# ADC.net
KiCad netlist of a schematic drawn in Altium Designer
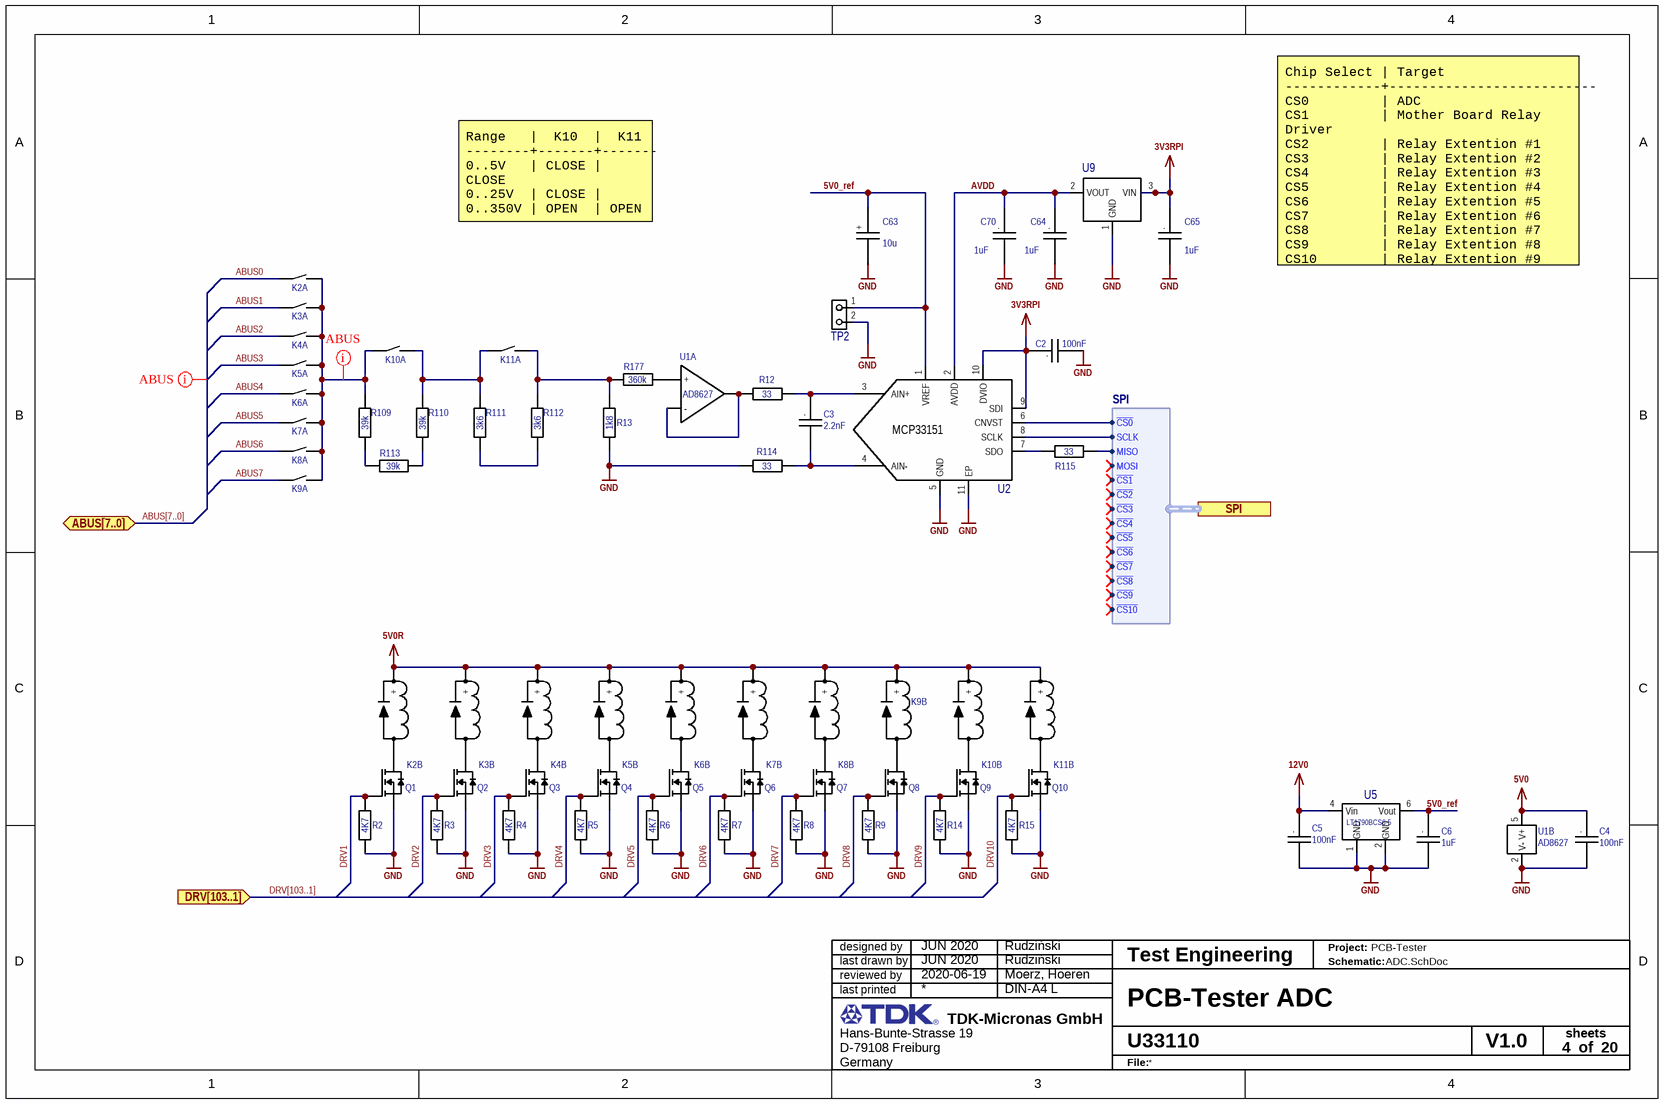
[diagram p0: ADC.SchDoc]

(export (version "E")
  (design (tool "Eeschema 10.0.6"))
  (components
    (comp (ref "C2")
      (value "100nF")
      (footprint "C0402 Reflow")
      (description "CAP CER 0.1UF 25V X7R 0402")
      (fields
        (field (name "TOLERANCE") "±5%")
        (field (name "02. DISTRIBUTOR PART NUMBER") "311-2077-6-ND")
        (field (name "13. CREATED DATE/NAME") "AUG2018/Hören")
      )
      (libsource (lib "chickenfood") (part "C"))
    )
    (comp (ref "C3")
      (value "2.2nF")
      (footprint "C0603 Reflow")
      (description "CAP CER 2200PF 50V X7R 0402")
      (fields
        (field (name "TOLERANCE") "±5%")
        (field (name "02. DISTRIBUTOR PART NUMBER") "1276-1532-6-ND")
        (field (name "13. CREATED DATE/NAME") "AUG2018/Hören")
      )
      (libsource (lib "chickenfood") (part "C"))
    )
    (comp (ref "C4")
      (value "100nF")
      (footprint "C0402 Reflow")
      (description "CAP CER 0.1UF 25V X7R 0402")
      (fields
        (field (name "TOLERANCE") "±5%")
        (field (name "02. DISTRIBUTOR PART NUMBER") "311-2077-6-ND")
        (field (name "13. CREATED DATE/NAME") "AUG2018/Hören")
      )
      (libsource (lib "chickenfood") (part "C"))
    )
    (comp (ref "C5")
      (value "100nF")
      (footprint "C0402 Reflow")
      (description "CAP CER 0.1UF 25V X7R 0402")
      (fields
        (field (name "TOLERANCE") "±5%")
        (field (name "02. DISTRIBUTOR PART NUMBER") "311-2077-6-ND")
        (field (name "13. CREATED DATE/NAME") "AUG2018/Hören")
      )
      (libsource (lib "chickenfood") (part "C"))
    )
    (comp (ref "C6")
      (value "1uF")
      (footprint "C0402 Reflow")
      (description "CAP CER 1UF 6.3V X7R 0402")
      (fields
        (field (name "TOLERANCE") "±10%")
        (field (name "02. DISTRIBUTOR PART NUMBER") "490-13339-6-ND")
        (field (name "13. CREATED DATE/NAME") "AUG2018/Hören")
      )
      (libsource (lib "chickenfood") (part "C"))
    )
    (comp (ref "C63")
      (value "10u")
      (footprint "CAP_TAN_B")
      (description "CAP TANT 10UF 20% 16V 1411")
      (fields
        (field (name "02. DISTRIBUTOR PART NUMBER") "718-2344-1-ND")
        (field (name "07. MANUFACTURER  PART NUMBER") "TMCHB1C106MTRF")
      )
      (libsource (lib "PCB-Tester-Board-V1") (part "C+_TAN"))
    )
    (comp (ref "C64")
      (value "1uF")
      (footprint "C0402 Reflow")
      (description "CAP CER 1UF 6.3V X7R 0402")
      (fields
        (field (name "TOLERANCE") "±10%")
        (field (name "02. DISTRIBUTOR PART NUMBER") "490-13339-6-ND")
        (field (name "13. CREATED DATE/NAME") "AUG2018/Hören")
      )
      (libsource (lib "chickenfood") (part "C"))
    )
    (comp (ref "C65")
      (value "1uF")
      (footprint "C0402 Reflow")
      (description "CAP CER 1UF 6.3V X7R 0402")
      (fields
        (field (name "TOLERANCE") "±10%")
        (field (name "02. DISTRIBUTOR PART NUMBER") "490-13339-6-ND")
        (field (name "13. CREATED DATE/NAME") "AUG2018/Hören")
      )
      (libsource (lib "chickenfood") (part "C"))
    )
    (comp (ref "C70")
      (value "1uF")
      (footprint "C0402 Reflow")
      (description "CAP CER 1UF 6.3V X7R 0402")
      (fields
        (field (name "TOLERANCE") "±10%")
        (field (name "02. DISTRIBUTOR PART NUMBER") "490-13339-6-ND")
        (field (name "13. CREATED DATE/NAME") "AUG2018/Hören")
      )
      (libsource (lib "chickenfood") (part "C"))
    )
    (comp (ref "K2")
      (value "K")
      (footprint "118-1A")
      (description "5V Signal Relais, Normal Open")
      (fields
        (field (name "02. DISTRIBUTOR PART NUMBER") "118-1-A-5/2D")
        (field (name "13. CREATED DATE/NAME") "20.12.17 S. Kaiser")
      )
      (libsource (lib "chickenfood") (part "118-1-A-5/2D"))
    )
    (comp (ref "K3")
      (value "K")
      (footprint "118-1A")
      (description "5V Signal Relais, Normal Open")
      (fields
        (field (name "02. DISTRIBUTOR PART NUMBER") "118-1-A-5/2D")
        (field (name "13. CREATED DATE/NAME") "20.12.17 S. Kaiser")
      )
      (libsource (lib "chickenfood") (part "118-1-A-5/2D"))
    )
    (comp (ref "K4")
      (value "K")
      (footprint "118-1A")
      (description "5V Signal Relais, Normal Open")
      (fields
        (field (name "02. DISTRIBUTOR PART NUMBER") "118-1-A-5/2D")
        (field (name "13. CREATED DATE/NAME") "20.12.17 S. Kaiser")
      )
      (libsource (lib "") (part "118-1-A-5/2D_1"))
    )
    (comp (ref "K5")
      (value "K")
      (footprint "118-1A")
      (description "5V Signal Relais, Normal Open")
      (fields
        (field (name "02. DISTRIBUTOR PART NUMBER") "118-1-A-5/2D")
        (field (name "13. CREATED DATE/NAME") "20.12.17 S. Kaiser")
      )
      (libsource (lib "chickenfood") (part "118-1-A-5/2D"))
    )
    (comp (ref "K6")
      (value "K")
      (footprint "118-1A")
      (description "5V Signal Relais, Normal Open")
      (fields
        (field (name "02. DISTRIBUTOR PART NUMBER") "118-1-A-5/2D")
        (field (name "13. CREATED DATE/NAME") "20.12.17 S. Kaiser")
      )
      (libsource (lib "") (part "118-1-A-5/2D_1"))
    )
    (comp (ref "K7")
      (value "K")
      (footprint "118-1A")
      (description "5V Signal Relais, Normal Open")
      (fields
        (field (name "02. DISTRIBUTOR PART NUMBER") "118-1-A-5/2D")
        (field (name "13. CREATED DATE/NAME") "20.12.17 S. Kaiser")
      )
      (libsource (lib "chickenfood") (part "118-1-A-5/2D"))
    )
    (comp (ref "K8")
      (value "K")
      (footprint "118-1A")
      (description "5V Signal Relais, Normal Open")
      (fields
        (field (name "02. DISTRIBUTOR PART NUMBER") "118-1-A-5/2D")
        (field (name "13. CREATED DATE/NAME") "20.12.17 S. Kaiser")
      )
      (libsource (lib "chickenfood") (part "118-1-A-5/2D"))
    )
    (comp (ref "K9")
      (value "K")
      (footprint "118-1A")
      (description "5V Signal Relais, Normal Open")
      (fields
        (field (name "02. DISTRIBUTOR PART NUMBER") "118-1-A-5/2D")
        (field (name "13. CREATED DATE/NAME") "20.12.17 S. Kaiser")
      )
      (libsource (lib "") (part "118-1-A-5/2D_1"))
    )
    (comp (ref "K10")
      (value "K")
      (footprint "118-1A")
      (description "5V Signal Relais, Normal Open")
      (fields
        (field (name "02. DISTRIBUTOR PART NUMBER") "118-1-A-5/2D")
        (field (name "13. CREATED DATE/NAME") "20.12.17 S. Kaiser")
      )
      (libsource (lib "chickenfood") (part "118-1-A-5/2D"))
    )
    (comp (ref "K11")
      (value "K")
      (footprint "118-1A")
      (description "5V Signal Relais, Normal Open")
      (fields
        (field (name "02. DISTRIBUTOR PART NUMBER") "118-1-A-5/2D")
        (field (name "13. CREATED DATE/NAME") "20.12.17 S. Kaiser")
      )
      (libsource (lib "chickenfood") (part "118-1-A-5/2D"))
    )
    (comp (ref "Q1")
      (value "Q")
      (footprint "SOT23-3")
      (description "MOSFET N-CH 25V 680MA SOT-23")
      (fields
        (field (name "02. DISTRIBUTOR PART NUMBER") "FDV303NDKR-ND")
        (field (name "07. MANUFACTURER  PART NUMBER") "FDV303N")
        (field (name "13. CREATED DATE/NAME") "AUG 2018 / Hören")
      )
      (libsource (lib "SCT8-Board1") (part "FDV303N"))
    )
    (comp (ref "Q2")
      (value "Q")
      (footprint "SOT23-3")
      (description "MOSFET N-CH 25V 680MA SOT-23")
      (fields
        (field (name "02. DISTRIBUTOR PART NUMBER") "FDV303NDKR-ND")
        (field (name "07. MANUFACTURER  PART NUMBER") "FDV303N")
        (field (name "13. CREATED DATE/NAME") "AUG 2018 / Hören")
      )
      (libsource (lib "SCT8-Board1") (part "FDV303N"))
    )
    (comp (ref "Q3")
      (value "Q")
      (footprint "SOT23-3")
      (description "MOSFET N-CH 25V 680MA SOT-23")
      (fields
        (field (name "02. DISTRIBUTOR PART NUMBER") "FDV303NDKR-ND")
        (field (name "07. MANUFACTURER  PART NUMBER") "FDV303N")
        (field (name "13. CREATED DATE/NAME") "AUG 2018 / Hören")
      )
      (libsource (lib "SCT8-Board1") (part "FDV303N"))
    )
    (comp (ref "Q4")
      (value "Q")
      (footprint "SOT23-3")
      (description "MOSFET N-CH 25V 680MA SOT-23")
      (fields
        (field (name "02. DISTRIBUTOR PART NUMBER") "FDV303NDKR-ND")
        (field (name "07. MANUFACTURER  PART NUMBER") "FDV303N")
        (field (name "13. CREATED DATE/NAME") "AUG 2018 / Hören")
      )
      (libsource (lib "SCT8-Board1") (part "FDV303N"))
    )
    (comp (ref "Q5")
      (value "Q")
      (footprint "SOT23-3")
      (description "MOSFET N-CH 25V 680MA SOT-23")
      (fields
        (field (name "02. DISTRIBUTOR PART NUMBER") "FDV303NDKR-ND")
        (field (name "07. MANUFACTURER  PART NUMBER") "FDV303N")
        (field (name "13. CREATED DATE/NAME") "AUG 2018 / Hören")
      )
      (libsource (lib "SCT8-Board1") (part "FDV303N"))
    )
    (comp (ref "Q6")
      (value "Q")
      (footprint "SOT23-3")
      (description "MOSFET N-CH 25V 680MA SOT-23")
      (fields
        (field (name "02. DISTRIBUTOR PART NUMBER") "FDV303NDKR-ND")
        (field (name "07. MANUFACTURER  PART NUMBER") "FDV303N")
        (field (name "13. CREATED DATE/NAME") "AUG 2018 / Hören")
      )
      (libsource (lib "SCT8-Board1") (part "FDV303N"))
    )
    (comp (ref "Q7")
      (value "Q")
      (footprint "SOT23-3")
      (description "MOSFET N-CH 25V 680MA SOT-23")
      (fields
        (field (name "02. DISTRIBUTOR PART NUMBER") "FDV303NDKR-ND")
        (field (name "07. MANUFACTURER  PART NUMBER") "FDV303N")
        (field (name "13. CREATED DATE/NAME") "AUG 2018 / Hören")
      )
      (libsource (lib "SCT8-Board1") (part "FDV303N"))
    )
    (comp (ref "Q8")
      (value "Q")
      (footprint "SOT23-3")
      (description "MOSFET N-CH 25V 680MA SOT-23")
      (fields
        (field (name "02. DISTRIBUTOR PART NUMBER") "FDV303NDKR-ND")
        (field (name "07. MANUFACTURER  PART NUMBER") "FDV303N")
        (field (name "13. CREATED DATE/NAME") "AUG 2018 / Hören")
      )
      (libsource (lib "SCT8-Board1") (part "FDV303N"))
    )
    (comp (ref "Q9")
      (value "Q")
      (footprint "SOT23-3")
      (description "MOSFET N-CH 25V 680MA SOT-23")
      (fields
        (field (name "02. DISTRIBUTOR PART NUMBER") "FDV303NDKR-ND")
        (field (name "07. MANUFACTURER  PART NUMBER") "FDV303N")
        (field (name "13. CREATED DATE/NAME") "AUG 2018 / Hören")
      )
      (libsource (lib "SCT8-Board1") (part "FDV303N"))
    )
    (comp (ref "Q10")
      (value "Q")
      (footprint "SOT23-3")
      (description "MOSFET N-CH 25V 680MA SOT-23")
      (fields
        (field (name "02. DISTRIBUTOR PART NUMBER") "FDV303NDKR-ND")
        (field (name "07. MANUFACTURER  PART NUMBER") "FDV303N")
        (field (name "13. CREATED DATE/NAME") "AUG 2018 / Hören")
      )
      (libsource (lib "SCT8-Board1") (part "FDV303N"))
    )
    (comp (ref "R2")
      (value "4K7")
      (footprint "R0603 Reflow")
      (description "RES SMD 4.7K OHM 1% 1/10W 0603")
      (fields
        (field (name "TOLERANCE") "±1%")
        (field (name "02. DISTRIBUTOR PART NUMBER") "311-4.70KHRCT-ND")
        (field (name "13. CREATED DATE/NAME") "AUG2018/Hören")
      )
      (libsource (lib "chickenfood") (part "R"))
    )
    (comp (ref "R3")
      (value "4K7")
      (footprint "R0603 Reflow")
      (description "RES SMD 4.7K OHM 1% 1/10W 0603")
      (fields
        (field (name "TOLERANCE") "±1%")
        (field (name "02. DISTRIBUTOR PART NUMBER") "311-4.70KHRCT-ND")
        (field (name "13. CREATED DATE/NAME") "AUG2018/Hören")
      )
      (libsource (lib "chickenfood") (part "R"))
    )
    (comp (ref "R4")
      (value "4K7")
      (footprint "R0603 Reflow")
      (description "RES SMD 4.7K OHM 1% 1/10W 0603")
      (fields
        (field (name "TOLERANCE") "±1%")
        (field (name "02. DISTRIBUTOR PART NUMBER") "311-4.70KHRCT-ND")
        (field (name "13. CREATED DATE/NAME") "AUG2018/Hören")
      )
      (libsource (lib "chickenfood") (part "R"))
    )
    (comp (ref "R5")
      (value "4K7")
      (footprint "R0603 Reflow")
      (description "RES SMD 4.7K OHM 1% 1/10W 0603")
      (fields
        (field (name "TOLERANCE") "±1%")
        (field (name "02. DISTRIBUTOR PART NUMBER") "311-4.70KHRCT-ND")
        (field (name "13. CREATED DATE/NAME") "AUG2018/Hören")
      )
      (libsource (lib "chickenfood") (part "R"))
    )
    (comp (ref "R6")
      (value "4K7")
      (footprint "R0603 Reflow")
      (description "RES SMD 4.7K OHM 1% 1/10W 0603")
      (fields
        (field (name "TOLERANCE") "±1%")
        (field (name "02. DISTRIBUTOR PART NUMBER") "311-4.70KHRCT-ND")
        (field (name "13. CREATED DATE/NAME") "AUG2018/Hören")
      )
      (libsource (lib "chickenfood") (part "R"))
    )
    (comp (ref "R7")
      (value "4K7")
      (footprint "R0603 Reflow")
      (description "RES SMD 4.7K OHM 1% 1/10W 0603")
      (fields
        (field (name "TOLERANCE") "±1%")
        (field (name "02. DISTRIBUTOR PART NUMBER") "311-4.70KHRCT-ND")
        (field (name "13. CREATED DATE/NAME") "AUG2018/Hören")
      )
      (libsource (lib "chickenfood") (part "R"))
    )
    (comp (ref "R8")
      (value "4K7")
      (footprint "R0603 Reflow")
      (description "RES SMD 4.7K OHM 1% 1/10W 0603")
      (fields
        (field (name "TOLERANCE") "±1%")
        (field (name "02. DISTRIBUTOR PART NUMBER") "311-4.70KHRCT-ND")
        (field (name "13. CREATED DATE/NAME") "AUG2018/Hören")
      )
      (libsource (lib "chickenfood") (part "R"))
    )
    (comp (ref "R9")
      (value "4K7")
      (footprint "R0603 Reflow")
      (description "RES SMD 4.7K OHM 1% 1/10W 0603")
      (fields
        (field (name "TOLERANCE") "±1%")
        (field (name "02. DISTRIBUTOR PART NUMBER") "311-4.70KHRCT-ND")
        (field (name "13. CREATED DATE/NAME") "AUG2018/Hören")
      )
      (libsource (lib "chickenfood") (part "R"))
    )
    (comp (ref "R12")
      (value "33")
      (footprint "R0402 Reflow")
      (description "RES SMD 33 OHM 1% 1/16W 0402")
      (fields
        (field (name "TOLERANCE") "±1%")
        (field (name "02. DISTRIBUTOR PART NUMBER") "311-33.0LRDKR-ND")
        (field (name "13. CREATED DATE/NAME") "AUG2018/Hören")
      )
      (libsource (lib "") (part "R_1"))
    )
    (comp (ref "R13")
      (value "1k8")
      (footprint "R0603 Reflow")
      (description "RES SMD 1.8K OHM 1% 1/16W 0402")
      (fields
        (field (name "TOLERANCE") "±1%")
        (field (name "02. DISTRIBUTOR PART NUMBER") "311-1.80KLRCT-ND")
        (field (name "13. CREATED DATE/NAME") "AUG2018/Hören")
      )
      (libsource (lib "chickenfood") (part "R"))
    )
    (comp (ref "R14")
      (value "4K7")
      (footprint "R0603 Reflow")
      (description "RES SMD 4.7K OHM 1% 1/10W 0603")
      (fields
        (field (name "TOLERANCE") "±1%")
        (field (name "02. DISTRIBUTOR PART NUMBER") "311-4.70KHRCT-ND")
        (field (name "13. CREATED DATE/NAME") "AUG2018/Hören")
      )
      (libsource (lib "chickenfood") (part "R"))
    )
    (comp (ref "R15")
      (value "4K7")
      (footprint "R0603 Reflow")
      (description "RES SMD 4.7K OHM 1% 1/10W 0603")
      (fields
        (field (name "TOLERANCE") "±1%")
        (field (name "02. DISTRIBUTOR PART NUMBER") "311-4.70KHRCT-ND")
        (field (name "13. CREATED DATE/NAME") "AUG2018/Hören")
      )
      (libsource (lib "chickenfood") (part "R"))
    )
    (comp (ref "R109")
      (value "39k")
      (footprint "R2512 Reflow")
      (description "CRGP 2512 39K 1%")
      (fields
        (field (name "TOLERANCE") "±1%")
        (field (name "02. DISTRIBUTOR PART NUMBER") "A130740CT-ND")
        (field (name "13. CREATED DATE/NAME") "AUG2018/Hören")
      )
      (libsource (lib "PCB-Tester-Board-V1") (part "R"))
    )
    (comp (ref "R110")
      (value "39k")
      (footprint "R2512 Reflow")
      (description "CRGP 2512 39K 1%")
      (fields
        (field (name "TOLERANCE") "±1%")
        (field (name "02. DISTRIBUTOR PART NUMBER") "A130740CT-ND")
        (field (name "13. CREATED DATE/NAME") "AUG2018/Hören")
      )
      (libsource (lib "PCB-Tester-Board-V1") (part "R"))
    )
    (comp (ref "R111")
      (value "3k6")
      (footprint "R0603 Reflow")
      (description "RES SMD 3.6K OHM 1% 1/10W 0603")
      (fields
        (field (name "TOLERANCE") "±1%")
        (field (name "02. DISTRIBUTOR PART NUMBER") "311-3.60KHRCT-ND")
        (field (name "13. CREATED DATE/NAME") "AUG2018/Hören")
      )
      (libsource (lib "PCB-Tester-Board-V1") (part "R"))
    )
    (comp (ref "R112")
      (value "3k6")
      (footprint "R0603 Reflow")
      (description "RES SMD 3.6K OHM 1% 1/10W 0603")
      (fields
        (field (name "TOLERANCE") "±1%")
        (field (name "02. DISTRIBUTOR PART NUMBER") "311-3.60KHRCT-ND")
        (field (name "13. CREATED DATE/NAME") "AUG2018/Hören")
      )
      (libsource (lib "PCB-Tester-Board-V1") (part "R"))
    )
    (comp (ref "R113")
      (value "39k")
      (footprint "R2512 Reflow")
      (description "CRGP 2512 39K 1%")
      (fields
        (field (name "TOLERANCE") "±1%")
        (field (name "02. DISTRIBUTOR PART NUMBER") "A130740CT-ND")
        (field (name "13. CREATED DATE/NAME") "AUG2018/Hören")
      )
      (libsource (lib "") (part "R_1"))
    )
    (comp (ref "R114")
      (value "33")
      (footprint "R0402 Reflow")
      (description "RES SMD 33 OHM 1% 1/16W 0402")
      (fields
        (field (name "TOLERANCE") "±1%")
        (field (name "02. DISTRIBUTOR PART NUMBER") "311-33.0LRDKR-ND")
        (field (name "13. CREATED DATE/NAME") "AUG2018/Hören")
      )
      (libsource (lib "") (part "R_1"))
    )
    (comp (ref "R115")
      (value "33")
      (footprint "R0402 Reflow")
      (description "RES SMD 33 OHM 1% 1/16W 0402")
      (fields
        (field (name "TOLERANCE") "±1%")
        (field (name "02. DISTRIBUTOR PART NUMBER") "311-33.0LRDKR-ND")
        (field (name "13. CREATED DATE/NAME") "AUG2018/Hören")
      )
      (libsource (lib "PCB-Tester-Board-V1") (part "R_19"))
    )
    (comp (ref "R177")
      (value "360k")
      (footprint "R1206 Reflow")
      (description "RES SMD 360K OHM 1% 1/4W 1206")
      (fields
        (field (name "TOLERANCE") "±1%")
        (field (name "02. DISTRIBUTOR PART NUMBER") "311-360KFRCT-ND")
        (field (name "13. CREATED DATE/NAME") "AUG2018/Hören")
      )
      (libsource (lib "") (part "R_1"))
    )
    (comp (ref "TP2")
      (value "TP")
      (footprint "DualTestpoint 100mils")
      (description "Dual testpoint, pitch 2.54mm")
      (fields
        (field (name "02. DISTRIBUTOR PART NUMBER") "HMTSW-103-07-G-S-240")
        (field (name "13. CREATED DATE/NAME") "AUG2018/Hören")
      )
      (libsource (lib "PCB-Tester-Board-V1") (part "DualTestpoint 100mils"))
    )
    (comp (ref "U1")
      (value "U")
      (footprint "tom:SC70-5")
      (description "IC OPAMP JFET 5MHZ RRO SC70-5")
      (fields
        (field (name "02. DISTRIBUTOR PART NUMBER") "AD8627AKSZ-R2DKR-ND")
        (field (name "07. MANUFACTURER  PART NUMBER") "AD8627AKSZ-R2")
        (field (name "PART") "AD8627")
        (field (name "13. CREATED DATE/NAME") "AUG 2018 / Hören")
      )
      (libsource (lib "tom") (part "AD8627"))
    )
    (comp (ref "U2")
      (value "U")
      (footprint "TDFN10EP")
      (description "14-BIT 1 MSPS SGL CH SGL-ENDED S")
      (fields
        (field (name "02. DISTRIBUTOR PART NUMBER") "MCP33151-10T-E/MNDKR-ND")
        (field (name "07. MANUFACTURER  PART NUMBER") "MCP33151-10T-E/MN")
        (field (name "NICNAME") "MCP33151")
        (field (name "13. CREATED DATE/NAME") "AUG 2018 / Hören")
      )
      (libsource (lib "tom") (part "MCP33151-10T-E/MN"))
    )
    (comp (ref "U5")
      (value "U")
      (footprint "TSOT23-6(S6)")
      (description "IC VREF SERIES 5V, 0.1% TSOT-23-6")
      (fields
        (field (name "02. DISTRIBUTOR PART NUMBER") "LT1790BCS6-5#TRMPBFDKR-ND")
        (field (name "07. MANUFACTURER  PART NUMBER") "LT1790BCS6-5#TRMPBF")
        (field (name "NICNAME") "LT1790BCS6-5")
        (field (name "13. CREATED DATE/NAME") "AUG 2018 / Hören")
      )
      (libsource (lib "tom") (part "LT1790BCS6-5"))
    )
    (comp (ref "U9")
      (value "U")
      (footprint "SOT23-3")
      (description "IC REG LINEAR 1.8V 250MA SOT23-3")
      (fields
        (field (name "02. DISTRIBUTOR PART NUMBER") "AP2138N-1.8TRG1DICT-ND")
        (field (name "07. MANUFACTURER  PART NUMBER") "AP2138N-1.8TRG1")
      )
      (libsource (lib "PCB-Tester-Board-V1") (part "AP2138N"))
    )
  )
  (nets
    (net (code "95") (name "/5V0_ref") (class "Default")
      (node (ref "C6") (pin "1") (pinfunction "1_1") (pintype "passive"))
      (node (ref "C63") (pin "1") (pinfunction "1_1") (pintype "passive"))
      (node (ref "TP2") (pin "1") (pinfunction "1_1") (pintype "passive"))
      (node (ref "U2") (pin "1") (pinfunction "VREF_1") (pintype "passive"))
      (node (ref "U5") (pin "6") (pinfunction "Vout_6") (pintype "passive"))
    )
    (net (code "96") (name "/ABUS0") (class "Default")
      (node (ref "K2") (pin "4") (pinfunction "CB_4") (pintype "passive"))
    )
    (net (code "97") (name "/ABUS1") (class "Default")
      (node (ref "K3") (pin "4") (pinfunction "CB_4") (pintype "passive"))
    )
    (net (code "98") (name "/ABUS2") (class "Default")
      (node (ref "K4") (pin "4") (pinfunction "CB_4") (pintype "passive"))
    )
    (net (code "99") (name "/ABUS3") (class "Default")
      (node (ref "K5") (pin "4") (pinfunction "CB_4") (pintype "passive"))
    )
    (net (code "100") (name "/ABUS4") (class "Default")
      (node (ref "K6") (pin "4") (pinfunction "CB_4") (pintype "passive"))
    )
    (net (code "101") (name "/ABUS5") (class "Default")
      (node (ref "K7") (pin "4") (pinfunction "CB_4") (pintype "passive"))
    )
    (net (code "102") (name "/ABUS6") (class "Default")
      (node (ref "K8") (pin "4") (pinfunction "CB_4") (pintype "passive"))
    )
    (net (code "103") (name "/ABUS7") (class "Default")
      (node (ref "K9") (pin "4") (pinfunction "CB_4") (pintype "passive"))
    )
    (net (code "105") (name "/AVDD") (class "Default")
      (node (ref "C64") (pin "1") (pinfunction "1_1") (pintype "passive"))
      (node (ref "C70") (pin "1") (pinfunction "1_1") (pintype "passive"))
      (node (ref "U2") (pin "2") (pinfunction "AVDD_2") (pintype "passive"))
      (node (ref "U9") (pin "2") (pinfunction "VOUT_2") (pintype "passive"))
    )
    (net (code "106") (name "/DRV1") (class "Default")
      (node (ref "Q1") (pin "1") (pinfunction "G_1") (pintype "passive"))
      (node (ref "R2") (pin "2") (pinfunction "2_2") (pintype "passive"))
    )
    (net (code "107") (name "/DRV2") (class "Default")
      (node (ref "Q2") (pin "1") (pinfunction "G_1") (pintype "passive"))
      (node (ref "R3") (pin "2") (pinfunction "2_2") (pintype "passive"))
    )
    (net (code "108") (name "/DRV3") (class "Default")
      (node (ref "Q3") (pin "1") (pinfunction "G_1") (pintype "passive"))
      (node (ref "R4") (pin "2") (pinfunction "2_2") (pintype "passive"))
    )
    (net (code "109") (name "/DRV4") (class "Default")
      (node (ref "Q4") (pin "1") (pinfunction "G_1") (pintype "passive"))
      (node (ref "R5") (pin "2") (pinfunction "2_2") (pintype "passive"))
    )
    (net (code "110") (name "/DRV5") (class "Default")
      (node (ref "Q5") (pin "1") (pinfunction "G_1") (pintype "passive"))
      (node (ref "R6") (pin "2") (pinfunction "2_2") (pintype "passive"))
    )
    (net (code "111") (name "/DRV6") (class "Default")
      (node (ref "Q6") (pin "1") (pinfunction "G_1") (pintype "passive"))
      (node (ref "R7") (pin "2") (pinfunction "2_2") (pintype "passive"))
    )
    (net (code "112") (name "/DRV7") (class "Default")
      (node (ref "Q7") (pin "1") (pinfunction "G_1") (pintype "passive"))
      (node (ref "R8") (pin "2") (pinfunction "2_2") (pintype "passive"))
    )
    (net (code "113") (name "/DRV8") (class "Default")
      (node (ref "Q8") (pin "1") (pinfunction "G_1") (pintype "passive"))
      (node (ref "R9") (pin "2") (pinfunction "2_2") (pintype "passive"))
    )
    (net (code "114") (name "/DRV9") (class "Default")
      (node (ref "Q9") (pin "1") (pinfunction "G_1") (pintype "passive"))
      (node (ref "R14") (pin "2") (pinfunction "2_2") (pintype "passive"))
    )
    (net (code "115") (name "/DRV10") (class "Default")
      (node (ref "Q10") (pin "1") (pinfunction "G_1") (pintype "passive"))
      (node (ref "R15") (pin "2") (pinfunction "2_2") (pintype "passive"))
    )
    (net (code "117") (name "/MISO") (class "Default")
      (node (ref "R115") (pin "2") (pinfunction "2_2") (pintype "passive"))
    )
    (net (code "118") (name "/SCLK") (class "Default")
      (node (ref "U2") (pin "8") (pinfunction "SCLK_8") (pintype "passive"))
    )
    (net (code "120") (name "/~{CS0}") (class "Default")
      (node (ref "U2") (pin "6") (pinfunction "CNVST_6") (pintype "passive"))
    )
    (net (code "121") (name "3V3RPI") (class "Default")
      (node (ref "C2") (pin "1") (pinfunction "1_1") (pintype "passive"))
      (node (ref "C65") (pin "1") (pinfunction "1_1") (pintype "passive"))
      (node (ref "U2") (pin "10") (pinfunction "DVIO_10") (pintype "passive"))
      (node (ref "U2") (pin "9") (pinfunction "SDI_9") (pintype "passive"))
      (node (ref "U9") (pin "3") (pinfunction "VIN_3") (pintype "passive"))
    )
    (net (code "122") (name "5V0") (class "Default")
      (node (ref "C4") (pin "1") (pinfunction "1_1") (pintype "passive"))
      (node (ref "U1") (pin "5") (pinfunction "V+_5") (pintype "passive"))
    )
    (net (code "123") (name "5V0R") (class "Default")
      (node (ref "K10") (pin "1") (pinfunction "+_1") (pintype "passive"))
      (node (ref "K11") (pin "1") (pinfunction "+_1") (pintype "passive"))
      (node (ref "K2") (pin "1") (pinfunction "+_1") (pintype "passive"))
      (node (ref "K3") (pin "1") (pinfunction "+_1") (pintype "passive"))
      (node (ref "K4") (pin "1") (pinfunction "+_1") (pintype "passive"))
      (node (ref "K5") (pin "1") (pinfunction "+_1") (pintype "passive"))
      (node (ref "K6") (pin "1") (pinfunction "+_1") (pintype "passive"))
      (node (ref "K7") (pin "1") (pinfunction "+_1") (pintype "passive"))
      (node (ref "K8") (pin "1") (pinfunction "+_1") (pintype "passive"))
      (node (ref "K9") (pin "1") (pinfunction "+_1") (pintype "passive"))
    )
    (net (code "124") (name "12V0") (class "Default")
      (node (ref "C5") (pin "1") (pinfunction "1_1") (pintype "passive"))
      (node (ref "U5") (pin "4") (pinfunction "Vin_4") (pintype "passive"))
    )
    (net (code "125") (name "GND") (class "Default")
      (node (ref "C2") (pin "2") (pinfunction "2_2") (pintype "passive"))
      (node (ref "C4") (pin "2") (pinfunction "2_2") (pintype "passive"))
      (node (ref "C5") (pin "2") (pinfunction "2_2") (pintype "passive"))
      (node (ref "C6") (pin "2") (pinfunction "2_2") (pintype "passive"))
      (node (ref "C63") (pin "2") (pinfunction "2_2") (pintype "passive"))
      (node (ref "C64") (pin "2") (pinfunction "2_2") (pintype "passive"))
      (node (ref "C65") (pin "2") (pinfunction "2_2") (pintype "passive"))
      (node (ref "C70") (pin "2") (pinfunction "2_2") (pintype "passive"))
      (node (ref "Q1") (pin "2") (pinfunction "S_2") (pintype "passive"))
      (node (ref "Q10") (pin "2") (pinfunction "S_2") (pintype "passive"))
      (node (ref "Q2") (pin "2") (pinfunction "S_2") (pintype "passive"))
      (node (ref "Q3") (pin "2") (pinfunction "S_2") (pintype "passive"))
      (node (ref "Q4") (pin "2") (pinfunction "S_2") (pintype "passive"))
      (node (ref "Q5") (pin "2") (pinfunction "S_2") (pintype "passive"))
      (node (ref "Q6") (pin "2") (pinfunction "S_2") (pintype "passive"))
      (node (ref "Q7") (pin "2") (pinfunction "S_2") (pintype "passive"))
      (node (ref "Q8") (pin "2") (pinfunction "S_2") (pintype "passive"))
      (node (ref "Q9") (pin "2") (pinfunction "S_2") (pintype "passive"))
      (node (ref "R114") (pin "2") (pinfunction "2_2") (pintype "passive"))
      (node (ref "R13") (pin "1") (pinfunction "1_1") (pintype "passive"))
      (node (ref "R14") (pin "1") (pinfunction "1_1") (pintype "passive"))
      (node (ref "R15") (pin "1") (pinfunction "1_1") (pintype "passive"))
      (node (ref "R2") (pin "1") (pinfunction "1_1") (pintype "passive"))
      (node (ref "R3") (pin "1") (pinfunction "1_1") (pintype "passive"))
      (node (ref "R4") (pin "1") (pinfunction "1_1") (pintype "passive"))
      (node (ref "R5") (pin "1") (pinfunction "1_1") (pintype "passive"))
      (node (ref "R6") (pin "1") (pinfunction "1_1") (pintype "passive"))
      (node (ref "R7") (pin "1") (pinfunction "1_1") (pintype "passive"))
      (node (ref "R8") (pin "1") (pinfunction "1_1") (pintype "passive"))
      (node (ref "R9") (pin "1") (pinfunction "1_1") (pintype "passive"))
      (node (ref "TP2") (pin "2") (pinfunction "2_2") (pintype "passive"))
      (node (ref "U1") (pin "2") (pinfunction "V-_2") (pintype "passive"))
      (node (ref "U2") (pin "11") (pinfunction "EP_11") (pintype "passive"))
      (node (ref "U2") (pin "5") (pinfunction "GND_5") (pintype "passive"))
      (node (ref "U5") (pin "1") (pinfunction "GND_1") (pintype "passive"))
      (node (ref "U5") (pin "2") (pinfunction "GND_2") (pintype "passive"))
      (node (ref "U9") (pin "1") (pinfunction "GND_1") (pintype "passive"))
    )
    (net (code "126") (name "Net-(K2B--)") (class "Default")
      (node (ref "K2") (pin "2") (pinfunction "-_2") (pintype "passive"))
      (node (ref "Q1") (pin "3") (pinfunction "D_3") (pintype "passive"))
    )
    (net (code "127") (name "Net-(K3B--)") (class "Default")
      (node (ref "K3") (pin "2") (pinfunction "-_2") (pintype "passive"))
      (node (ref "Q2") (pin "3") (pinfunction "D_3") (pintype "passive"))
    )
    (net (code "128") (name "Net-(K4B--)") (class "Default")
      (node (ref "K4") (pin "2") (pinfunction "-_2") (pintype "passive"))
      (node (ref "Q3") (pin "3") (pinfunction "D_3") (pintype "passive"))
    )
    (net (code "129") (name "Net-(K5B--)") (class "Default")
      (node (ref "K5") (pin "2") (pinfunction "-_2") (pintype "passive"))
      (node (ref "Q4") (pin "3") (pinfunction "D_3") (pintype "passive"))
    )
    (net (code "130") (name "Net-(K6B--)") (class "Default")
      (node (ref "K6") (pin "2") (pinfunction "-_2") (pintype "passive"))
      (node (ref "Q5") (pin "3") (pinfunction "D_3") (pintype "passive"))
    )
    (net (code "131") (name "Net-(K7B--)") (class "Default")
      (node (ref "K7") (pin "2") (pinfunction "-_2") (pintype "passive"))
      (node (ref "Q6") (pin "3") (pinfunction "D_3") (pintype "passive"))
    )
    (net (code "132") (name "Net-(K8B--)") (class "Default")
      (node (ref "K8") (pin "2") (pinfunction "-_2") (pintype "passive"))
      (node (ref "Q7") (pin "3") (pinfunction "D_3") (pintype "passive"))
    )
    (net (code "133") (name "Net-(K9B--)") (class "Default")
      (node (ref "K9") (pin "2") (pinfunction "-_2") (pintype "passive"))
      (node (ref "Q8") (pin "3") (pinfunction "D_3") (pintype "passive"))
    )
    (net (code "134") (name "Net-(K10A-CA)") (class "Default")
      (node (ref "K10") (pin "3") (pinfunction "CA_3") (pintype "passive"))
      (node (ref "K11") (pin "4") (pinfunction "CB_4") (pintype "passive"))
      (node (ref "R110") (pin "2") (pinfunction "2_2") (pintype "passive"))
      (node (ref "R111") (pin "2") (pinfunction "2_2") (pintype "passive"))
    )
    (net (code "135") (name "Net-(K10A-CB)") (class "Default")
      (node (ref "K10") (pin "4") (pinfunction "CB_4") (pintype "passive"))
      (node (ref "K2") (pin "3") (pinfunction "CA_3") (pintype "passive"))
      (node (ref "K3") (pin "3") (pinfunction "CA_3") (pintype "passive"))
      (node (ref "K4") (pin "3") (pinfunction "CA_3") (pintype "passive"))
      (node (ref "K5") (pin "3") (pinfunction "CA_3") (pintype "passive"))
      (node (ref "K6") (pin "3") (pinfunction "CA_3") (pintype "passive"))
      (node (ref "K7") (pin "3") (pinfunction "CA_3") (pintype "passive"))
      (node (ref "K8") (pin "3") (pinfunction "CA_3") (pintype "passive"))
      (node (ref "K9") (pin "3") (pinfunction "CA_3") (pintype "passive"))
      (node (ref "R109") (pin "2") (pinfunction "2_2") (pintype "passive"))
    )
    (net (code "136") (name "Net-(K10B--)") (class "Default")
      (node (ref "K10") (pin "2") (pinfunction "-_2") (pintype "passive"))
      (node (ref "Q9") (pin "3") (pinfunction "D_3") (pintype "passive"))
    )
    (net (code "137") (name "Net-(K11A-CA)") (class "Default")
      (node (ref "K11") (pin "3") (pinfunction "CA_3") (pintype "passive"))
      (node (ref "R112") (pin "2") (pinfunction "2_2") (pintype "passive"))
      (node (ref "R13") (pin "2") (pinfunction "2_2") (pintype "passive"))
      (node (ref "R177") (pin "2") (pinfunction "2_2") (pintype "passive"))
    )
    (net (code "138") (name "Net-(K11B--)") (class "Default")
      (node (ref "K11") (pin "2") (pinfunction "-_2") (pintype "passive"))
      (node (ref "Q10") (pin "3") (pinfunction "D_3") (pintype "passive"))
    )
    (net (code "139") (name "Net-(R109-Pad1)") (class "Default")
      (node (ref "R109") (pin "1") (pinfunction "1_1") (pintype "passive"))
      (node (ref "R113") (pin "2") (pinfunction "2_2") (pintype "passive"))
    )
    (net (code "140") (name "Net-(R110-Pad1)") (class "Default")
      (node (ref "R110") (pin "1") (pinfunction "1_1") (pintype "passive"))
      (node (ref "R113") (pin "1") (pinfunction "1_1") (pintype "passive"))
    )
    (net (code "141") (name "Net-(R111-Pad1)") (class "Default")
      (node (ref "R111") (pin "1") (pinfunction "1_1") (pintype "passive"))
      (node (ref "R112") (pin "1") (pinfunction "1_1") (pintype "passive"))
    )
    (net (code "142") (name "Net-(U1A-+)") (class "Default")
      (node (ref "R177") (pin "1") (pinfunction "1_1") (pintype "passive"))
      (node (ref "U1") (pin "3") (pinfunction "+_3") (pintype "passive"))
    )
    (net (code "143") (name "Net-(U1A--)") (class "Default")
      (node (ref "R12") (pin "2") (pinfunction "2_2") (pintype "passive"))
      (node (ref "U1") (pin "1") (pinfunction "Out_1") (pintype "passive"))
      (node (ref "U1") (pin "4") (pinfunction "-_4") (pintype "passive"))
    )
    (net (code "144") (name "Net-(U2-AIN+)") (class "Default")
      (node (ref "C3") (pin "1") (pinfunction "1_1") (pintype "passive"))
      (node (ref "R12") (pin "1") (pinfunction "1_1") (pintype "passive"))
      (node (ref "U2") (pin "3") (pinfunction "AIN+_3") (pintype "passive"))
    )
    (net (code "145") (name "Net-(U2-AIN-)") (class "Default")
      (node (ref "C3") (pin "2") (pinfunction "2_2") (pintype "passive"))
      (node (ref "R114") (pin "1") (pinfunction "1_1") (pintype "passive"))
      (node (ref "U2") (pin "4") (pinfunction "AIN-_4") (pintype "passive"))
    )
    (net (code "146") (name "Net-(U2-SDO)") (class "Default")
      (node (ref "R115") (pin "1") (pinfunction "1_1") (pintype "passive"))
      (node (ref "U2") (pin "7") (pinfunction "SDO_7") (pintype "passive"))
    )
  )
)
